# Kenbak-nanoduino.net
KiCad netlist of a schematic drawn in EAGLE
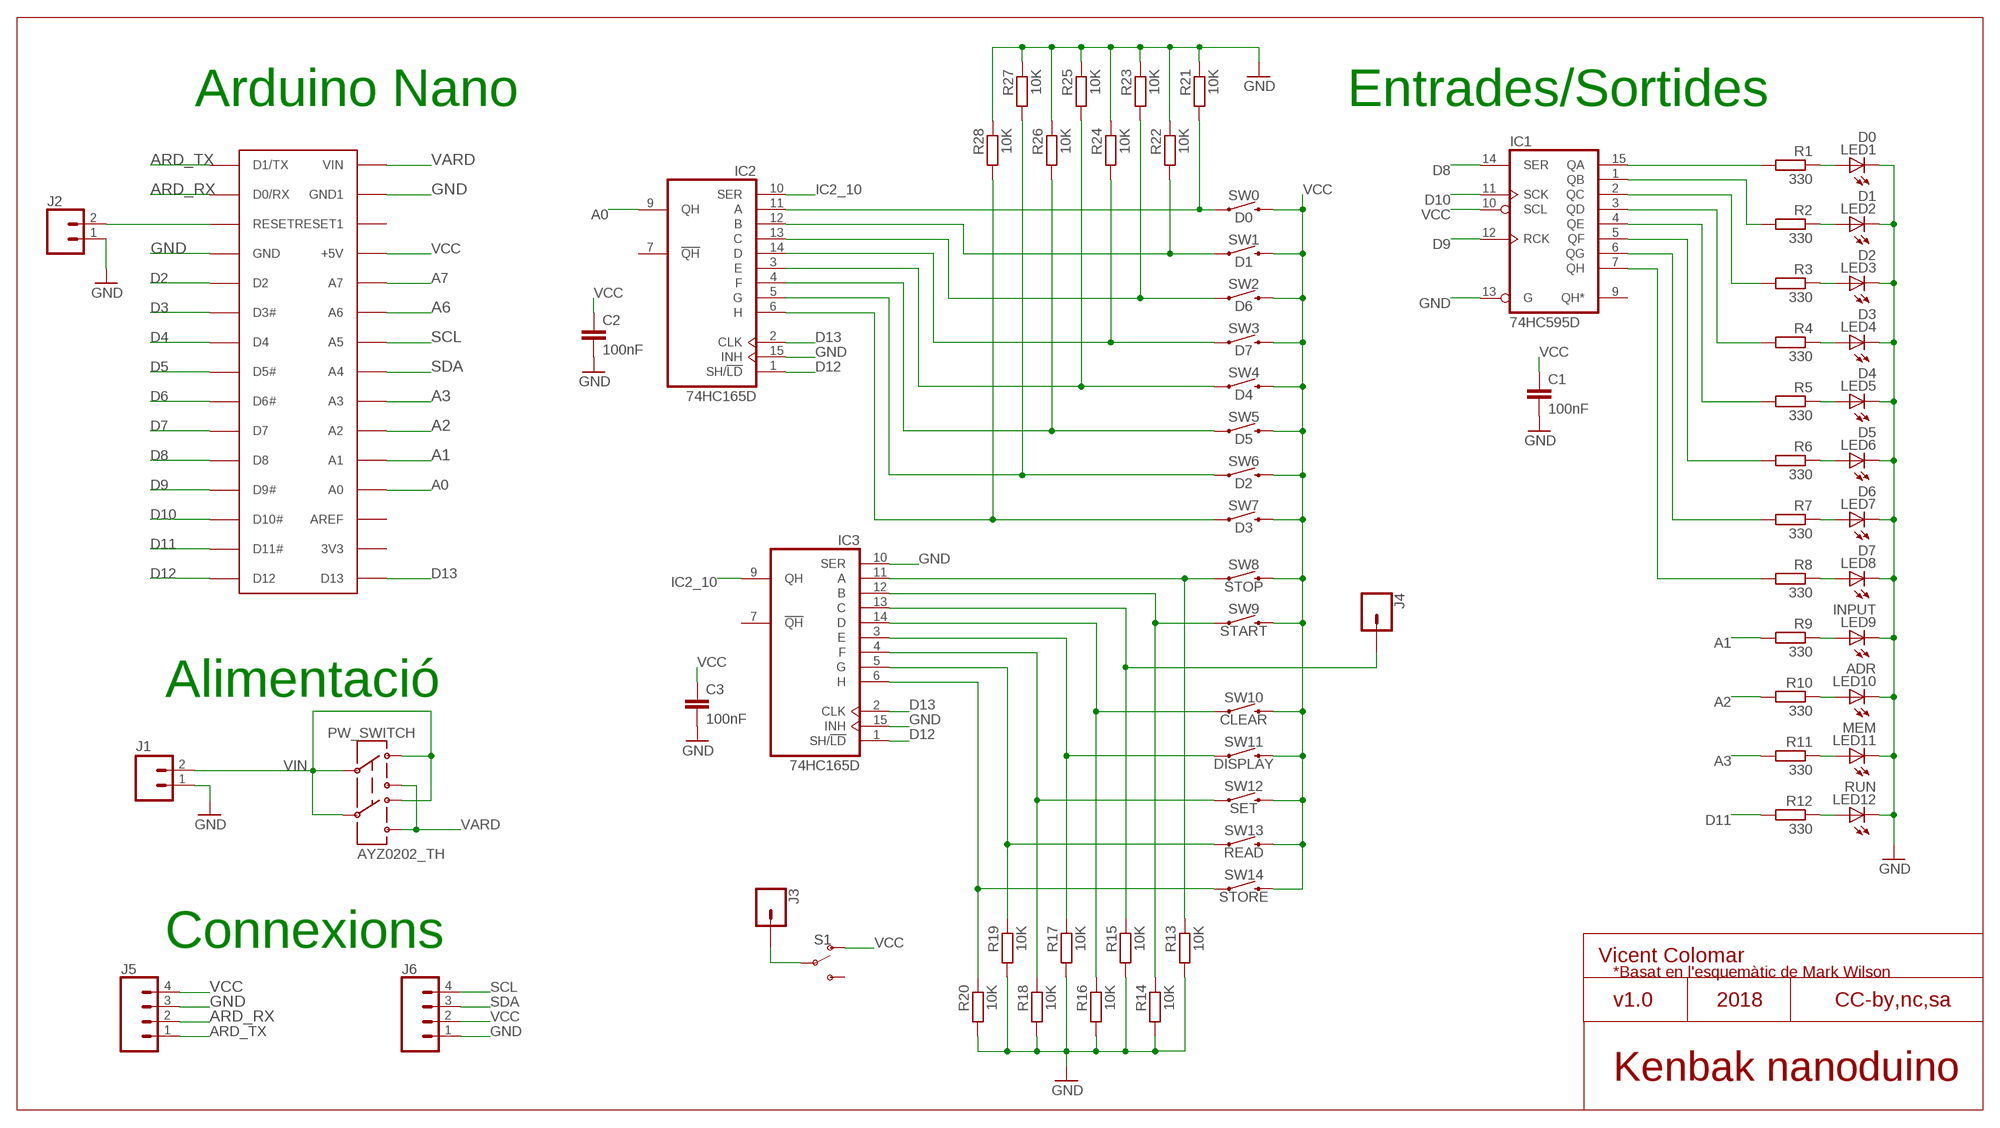
[diagram p0: schematic, sheet 1]

(export (version "E")
  (design (tool "Eeschema 10.0.6"))
  (components
    (comp (ref "ARDUINO")
      (value "NANO")
      (footprint "eagle-import:PDIP-32NOHOLES")
      (libsource (lib "eagle-import") (part "ARDUINONANONOHOLES"))
    )
    (comp (ref "C1")
      (value "100nF")
      (footprint "eagle-import:C1206")
      (libsource (lib "eagle-import") (part "C-EUC1206"))
    )
    (comp (ref "C2")
      (value "100nF")
      (footprint "eagle-import:C1206")
      (libsource (lib "eagle-import") (part "C-EUC1206"))
    )
    (comp (ref "C3")
      (value "100nF")
      (footprint "eagle-import:C1206")
      (libsource (lib "eagle-import") (part "C-EUC1206"))
    )
    (comp (ref "IC1")
      (value "74HC595D")
      (footprint "eagle-import:SO16")
      (libsource (lib "eagle-import") (part "74595DHC"))
    )
    (comp (ref "IC2")
      (value "74HC165D")
      (footprint "eagle-import:SO16")
      (libsource (lib "eagle-import") (part "74165DHC"))
    )
    (comp (ref "IC3")
      (value "74HC165D")
      (footprint "eagle-import:SO16")
      (libsource (lib "eagle-import") (part "74165DHC"))
    )
    (comp (ref "J1")
      (value "M02LOCK_LONGPADS")
      (footprint "eagle-import:1X02_LOCK_LONGPADS")
      (libsource (lib "eagle-import") (part "M02LOCK_LONGPADS"))
    )
    (comp (ref "J2")
      (value "CONN_02")
      (footprint "eagle-import:1X02")
      (libsource (lib "eagle-import") (part "CONN_02"))
    )
    (comp (ref "J3")
      (value "CONN_01")
      (footprint "eagle-import:1X01")
      (libsource (lib "eagle-import") (part "CONN_01"))
    )
    (comp (ref "J4")
      (value "CONN_01")
      (footprint "eagle-import:1X01")
      (libsource (lib "eagle-import") (part "CONN_01"))
    )
    (comp (ref "J5")
      (value "CONN_04")
      (footprint "eagle-import:1X04")
      (libsource (lib "eagle-import") (part "CONN_04"))
    )
    (comp (ref "J6")
      (value "CONN_04")
      (footprint "eagle-import:1X04")
      (libsource (lib "eagle-import") (part "CONN_04"))
    )
    (comp (ref "LED1")
      (value "D0")
      (footprint "eagle-import:LED3MM")
      (libsource (lib "eagle-import") (part "LED3MM"))
    )
    (comp (ref "LED2")
      (value "D1")
      (footprint "eagle-import:LED3MM")
      (libsource (lib "eagle-import") (part "LED3MM"))
    )
    (comp (ref "LED3")
      (value "D2")
      (footprint "eagle-import:LED3MM")
      (libsource (lib "eagle-import") (part "LED3MM"))
    )
    (comp (ref "LED4")
      (value "D3")
      (footprint "eagle-import:LED3MM")
      (libsource (lib "eagle-import") (part "LED3MM"))
    )
    (comp (ref "LED5")
      (value "D4")
      (footprint "eagle-import:LED3MM")
      (libsource (lib "eagle-import") (part "LED3MM"))
    )
    (comp (ref "LED6")
      (value "D5")
      (footprint "eagle-import:LED3MM")
      (libsource (lib "eagle-import") (part "LED3MM"))
    )
    (comp (ref "LED7")
      (value "D6")
      (footprint "eagle-import:LED3MM")
      (libsource (lib "eagle-import") (part "LED3MM"))
    )
    (comp (ref "LED8")
      (value "D7")
      (footprint "eagle-import:LED3MM")
      (libsource (lib "eagle-import") (part "LED3MM"))
    )
    (comp (ref "LED9")
      (value "INPUT")
      (footprint "eagle-import:LED3MM")
      (libsource (lib "eagle-import") (part "LED3MM"))
    )
    (comp (ref "LED10")
      (value "ADR")
      (footprint "eagle-import:LED3MM")
      (libsource (lib "eagle-import") (part "LED3MM"))
    )
    (comp (ref "LED11")
      (value "MEM")
      (footprint "eagle-import:LED3MM")
      (libsource (lib "eagle-import") (part "LED3MM"))
    )
    (comp (ref "LED12")
      (value "RUN")
      (footprint "eagle-import:LED3MM")
      (libsource (lib "eagle-import") (part "LED3MM"))
    )
    (comp (ref "PW_SWITCH")
      (value "AYZ0202_TH")
      (footprint "eagle-import:AYZ0202_TH")
      (libsource (lib "eagle-import") (part "AYZ0202_TH"))
    )
    (comp (ref "R1")
      (value "330")
      (footprint "eagle-import:R1206")
      (libsource (lib "eagle-import") (part "R-EU_R1206"))
    )
    (comp (ref "R2")
      (value "330")
      (footprint "eagle-import:R1206")
      (libsource (lib "eagle-import") (part "R-EU_R1206"))
    )
    (comp (ref "R3")
      (value "330")
      (footprint "eagle-import:R1206")
      (libsource (lib "eagle-import") (part "R-EU_R1206"))
    )
    (comp (ref "R4")
      (value "330")
      (footprint "eagle-import:R1206")
      (libsource (lib "eagle-import") (part "R-EU_R1206"))
    )
    (comp (ref "R5")
      (value "330")
      (footprint "eagle-import:R1206")
      (libsource (lib "eagle-import") (part "R-EU_R1206"))
    )
    (comp (ref "R6")
      (value "330")
      (footprint "eagle-import:R1206")
      (libsource (lib "eagle-import") (part "R-EU_R1206"))
    )
    (comp (ref "R7")
      (value "330")
      (footprint "eagle-import:R1206")
      (libsource (lib "eagle-import") (part "R-EU_R1206"))
    )
    (comp (ref "R8")
      (value "330")
      (footprint "eagle-import:R1206")
      (libsource (lib "eagle-import") (part "R-EU_R1206"))
    )
    (comp (ref "R9")
      (value "330")
      (footprint "eagle-import:R1206")
      (libsource (lib "eagle-import") (part "R-EU_R1206"))
    )
    (comp (ref "R10")
      (value "330")
      (footprint "eagle-import:R1206")
      (libsource (lib "eagle-import") (part "R-EU_R1206"))
    )
    (comp (ref "R11")
      (value "330")
      (footprint "eagle-import:R1206")
      (libsource (lib "eagle-import") (part "R-EU_R1206"))
    )
    (comp (ref "R12")
      (value "330")
      (footprint "eagle-import:R1206")
      (libsource (lib "eagle-import") (part "R-EU_R1206"))
    )
    (comp (ref "R13")
      (value "10K")
      (footprint "eagle-import:R1206")
      (libsource (lib "eagle-import") (part "R-EU_R1206"))
    )
    (comp (ref "R14")
      (value "10K")
      (footprint "eagle-import:R1206")
      (libsource (lib "eagle-import") (part "R-EU_R1206"))
    )
    (comp (ref "R15")
      (value "10K")
      (footprint "eagle-import:R1206")
      (libsource (lib "eagle-import") (part "R-EU_R1206"))
    )
    (comp (ref "R16")
      (value "10K")
      (footprint "eagle-import:R1206")
      (libsource (lib "eagle-import") (part "R-EU_R1206"))
    )
    (comp (ref "R17")
      (value "10K")
      (footprint "eagle-import:R1206")
      (libsource (lib "eagle-import") (part "R-EU_R1206"))
    )
    (comp (ref "R18")
      (value "10K")
      (footprint "eagle-import:R1206")
      (libsource (lib "eagle-import") (part "R-EU_R1206"))
    )
    (comp (ref "R19")
      (value "10K")
      (footprint "eagle-import:R1206")
      (libsource (lib "eagle-import") (part "R-EU_R1206"))
    )
    (comp (ref "R20")
      (value "10K")
      (footprint "eagle-import:R1206")
      (libsource (lib "eagle-import") (part "R-EU_R1206"))
    )
    (comp (ref "R21")
      (value "10K")
      (footprint "eagle-import:R1206")
      (libsource (lib "eagle-import") (part "R-EU_R1206"))
    )
    (comp (ref "R22")
      (value "10K")
      (footprint "eagle-import:R1206")
      (libsource (lib "eagle-import") (part "R-EU_R1206"))
    )
    (comp (ref "R23")
      (value "10K")
      (footprint "eagle-import:R1206")
      (libsource (lib "eagle-import") (part "R-EU_R1206"))
    )
    (comp (ref "R24")
      (value "10K")
      (footprint "eagle-import:R1206")
      (libsource (lib "eagle-import") (part "R-EU_R1206"))
    )
    (comp (ref "R25")
      (value "10K")
      (footprint "eagle-import:R1206")
      (libsource (lib "eagle-import") (part "R-EU_R1206"))
    )
    (comp (ref "R26")
      (value "10K")
      (footprint "eagle-import:R1206")
      (libsource (lib "eagle-import") (part "R-EU_R1206"))
    )
    (comp (ref "R27")
      (value "10K")
      (footprint "eagle-import:R1206")
      (libsource (lib "eagle-import") (part "R-EU_R1206"))
    )
    (comp (ref "R28")
      (value "10K")
      (footprint "eagle-import:R1206")
      (libsource (lib "eagle-import") (part "R-EU_R1206"))
    )
    (comp (ref "S1")
      (value "SWITCH-SPDT-PTH-11.6X4.0MM")
      (footprint "eagle-import:SWITCH_SPDT_PTH_11.6X4.0MM")
      (libsource (lib "eagle-import") (part "SWITCH-SPDT-PTH-11.6X4.0MM"))
    )
    (comp (ref "SW0")
      (value "D0")
      (footprint "eagle-import:TACTILE_SWITCH_PTH_6.0X3.5MM")
      (libsource (lib "eagle-import") (part "BOTOPTH"))
    )
    (comp (ref "SW1")
      (value "D1")
      (footprint "eagle-import:TACTILE_SWITCH_PTH_6.0X3.5MM")
      (libsource (lib "eagle-import") (part "BOTOPTH"))
    )
    (comp (ref "SW2")
      (value "D6")
      (footprint "eagle-import:TACTILE_SWITCH_PTH_6.0X3.5MM")
      (libsource (lib "eagle-import") (part "BOTOPTH"))
    )
    (comp (ref "SW3")
      (value "D7")
      (footprint "eagle-import:TACTILE_SWITCH_PTH_6.0X3.5MM")
      (libsource (lib "eagle-import") (part "BOTOPTH"))
    )
    (comp (ref "SW4")
      (value "D4")
      (footprint "eagle-import:TACTILE_SWITCH_PTH_6.0X3.5MM")
      (libsource (lib "eagle-import") (part "BOTOPTH"))
    )
    (comp (ref "SW5")
      (value "D5")
      (footprint "eagle-import:TACTILE_SWITCH_PTH_6.0X3.5MM")
      (libsource (lib "eagle-import") (part "BOTOPTH"))
    )
    (comp (ref "SW6")
      (value "D2")
      (footprint "eagle-import:TACTILE_SWITCH_PTH_6.0X3.5MM")
      (libsource (lib "eagle-import") (part "BOTOPTH"))
    )
    (comp (ref "SW7")
      (value "D3")
      (footprint "eagle-import:TACTILE_SWITCH_PTH_6.0X3.5MM")
      (libsource (lib "eagle-import") (part "BOTOPTH"))
    )
    (comp (ref "SW8")
      (value "STOP")
      (footprint "eagle-import:TACTILE_SWITCH_PTH_6.0X3.5MM")
      (libsource (lib "eagle-import") (part "BOTOPTH"))
    )
    (comp (ref "SW9")
      (value "START")
      (footprint "eagle-import:TACTILE_SWITCH_PTH_6.0X3.5MM")
      (libsource (lib "eagle-import") (part "BOTOPTH"))
    )
    (comp (ref "SW10")
      (value "CLEAR")
      (footprint "eagle-import:TACTILE_SWITCH_PTH_6.0X3.5MM")
      (libsource (lib "eagle-import") (part "BOTOPTH"))
    )
    (comp (ref "SW11")
      (value "DISPLAY")
      (footprint "eagle-import:TACTILE_SWITCH_PTH_6.0X3.5MM")
      (libsource (lib "eagle-import") (part "BOTOPTH"))
    )
    (comp (ref "SW12")
      (value "SET")
      (footprint "eagle-import:TACTILE_SWITCH_PTH_6.0X3.5MM")
      (libsource (lib "eagle-import") (part "BOTOPTH"))
    )
    (comp (ref "SW13")
      (value "READ")
      (footprint "eagle-import:TACTILE_SWITCH_PTH_6.0X3.5MM")
      (libsource (lib "eagle-import") (part "BOTOPTH"))
    )
    (comp (ref "SW14")
      (value "STORE")
      (footprint "eagle-import:TACTILE_SWITCH_PTH_6.0X3.5MM")
      (libsource (lib "eagle-import") (part "BOTOPTH"))
    )
  )
  (nets
    (net (code "1") (name "/A0") (class "Default")
      (node (ref "ARDUINO") (pin "A0") (pinfunction "A0_A0") (pintype "bidirectional"))
      (node (ref "IC2") (pin "9") (pinfunction "QH_9") (pintype "output"))
    )
    (net (code "2") (name "/A1") (class "Default")
      (node (ref "ARDUINO") (pin "A1") (pinfunction "A1_A1") (pintype "bidirectional"))
      (node (ref "R9") (pin "2") (pinfunction "2_2") (pintype "passive"))
    )
    (net (code "3") (name "/A2") (class "Default")
      (node (ref "ARDUINO") (pin "A2") (pinfunction "A2_A2") (pintype "bidirectional"))
      (node (ref "R10") (pin "2") (pinfunction "2_2") (pintype "passive"))
    )
    (net (code "4") (name "/A3") (class "Default")
      (node (ref "ARDUINO") (pin "A3") (pinfunction "A3_A3") (pintype "bidirectional"))
      (node (ref "R11") (pin "2") (pinfunction "2_2") (pintype "passive"))
    )
    (net (code "5") (name "/A6") (class "Default")
      (node (ref "ARDUINO") (pin "A6") (pinfunction "A6_A6") (pintype "bidirectional"))
    )
    (net (code "6") (name "/A7") (class "Default")
      (node (ref "ARDUINO") (pin "A7") (pinfunction "A7_A7") (pintype "bidirectional"))
    )
    (net (code "7") (name "/ARD_RX") (class "Default")
      (node (ref "ARDUINO") (pin "D0/RX") (pinfunction "D0/RX_D0/RX") (pintype "bidirectional"))
      (node (ref "J5") (pin "2") (pinfunction "2_2") (pintype "passive"))
    )
    (net (code "8") (name "/ARD_TX") (class "Default")
      (node (ref "ARDUINO") (pin "D1/TX") (pinfunction "D1/TX_D1/TX") (pintype "bidirectional"))
      (node (ref "J5") (pin "1") (pinfunction "1_1") (pintype "passive"))
    )
    (net (code "9") (name "/D2") (class "Default")
      (node (ref "ARDUINO") (pin "D2") (pinfunction "D2_D2") (pintype "bidirectional"))
    )
    (net (code "10") (name "/D3") (class "Default")
      (node (ref "ARDUINO") (pin "D3") (pinfunction "D3#_D3") (pintype "bidirectional"))
    )
    (net (code "11") (name "/D4") (class "Default")
      (node (ref "ARDUINO") (pin "D4") (pinfunction "D4_D4") (pintype "bidirectional"))
    )
    (net (code "12") (name "/D5") (class "Default")
      (node (ref "ARDUINO") (pin "D5") (pinfunction "D5#_D5") (pintype "bidirectional"))
    )
    (net (code "13") (name "/D6") (class "Default")
      (node (ref "ARDUINO") (pin "D6") (pinfunction "D6#_D6") (pintype "bidirectional"))
    )
    (net (code "14") (name "/D7") (class "Default")
      (node (ref "ARDUINO") (pin "D7") (pinfunction "D7_D7") (pintype "bidirectional"))
    )
    (net (code "15") (name "/D8") (class "Default")
      (node (ref "ARDUINO") (pin "D8") (pinfunction "D8_D8") (pintype "bidirectional"))
      (node (ref "IC1") (pin "14") (pinfunction "SER_14") (pintype "input"))
    )
    (net (code "16") (name "/D9") (class "Default")
      (node (ref "ARDUINO") (pin "D9") (pinfunction "D9#_D9") (pintype "bidirectional"))
      (node (ref "IC1") (pin "12") (pinfunction "RCK_12") (pintype "input"))
    )
    (net (code "17") (name "/D10") (class "Default")
      (node (ref "ARDUINO") (pin "D10") (pinfunction "D10#_D10") (pintype "bidirectional"))
      (node (ref "IC1") (pin "11") (pinfunction "SCK_11") (pintype "input"))
    )
    (net (code "18") (name "/D11") (class "Default")
      (node (ref "ARDUINO") (pin "D11") (pinfunction "D11#_D11") (pintype "bidirectional"))
      (node (ref "R12") (pin "2") (pinfunction "2_2") (pintype "passive"))
    )
    (net (code "19") (name "/D12") (class "Default")
      (node (ref "ARDUINO") (pin "D12") (pinfunction "D12_D12") (pintype "bidirectional"))
      (node (ref "IC2") (pin "1") (pinfunction "SH/~{LD}_1") (pintype "input"))
      (node (ref "IC3") (pin "1") (pinfunction "SH/~{LD}_1") (pintype "input"))
    )
    (net (code "20") (name "/D13") (class "Default")
      (node (ref "ARDUINO") (pin "D13") (pinfunction "D13_D13") (pintype "bidirectional"))
      (node (ref "IC2") (pin "2") (pinfunction "CLK_2") (pintype "input"))
      (node (ref "IC3") (pin "2") (pinfunction "CLK_2") (pintype "input"))
    )
    (net (code "21") (name "/IC2_10") (class "Default")
      (node (ref "IC2") (pin "10") (pinfunction "SER_10") (pintype "input"))
      (node (ref "IC3") (pin "9") (pinfunction "QH_9") (pintype "output"))
    )
    (net (code "22") (name "/SCL") (class "Default")
      (node (ref "ARDUINO") (pin "A5") (pinfunction "A5_A5") (pintype "bidirectional"))
      (node (ref "J6") (pin "4") (pinfunction "4_4") (pintype "passive"))
    )
    (net (code "23") (name "/SDA") (class "Default")
      (node (ref "ARDUINO") (pin "A4") (pinfunction "A4_A4") (pintype "bidirectional"))
      (node (ref "J6") (pin "3") (pinfunction "3_3") (pintype "passive"))
    )
    (net (code "24") (name "/VARD") (class "Default")
      (node (ref "ARDUINO") (pin "VIN") (pinfunction "VIN_VIN") (pintype "bidirectional"))
      (node (ref "PW_SWITCH") (pin "B1") (pinfunction "B1_B1") (pintype "bidirectional"))
      (node (ref "PW_SWITCH") (pin "B2") (pinfunction "B2_B2") (pintype "bidirectional"))
    )
    (net (code "25") (name "/VCC") (class "Default")
      (node (ref "ARDUINO") (pin "+5V") (pinfunction "+5V_+5V") (pintype "bidirectional"))
      (node (ref "C1") (pin "1") (pinfunction "1_1") (pintype "passive"))
      (node (ref "C2") (pin "1") (pinfunction "1_1") (pintype "passive"))
      (node (ref "C3") (pin "1") (pinfunction "1_1") (pintype "passive"))
      (node (ref "IC1") (pin "10") (pinfunction "SCL_10") (pintype "input"))
      (node (ref "J5") (pin "4") (pinfunction "4_4") (pintype "passive"))
      (node (ref "J6") (pin "2") (pinfunction "2_2") (pintype "passive"))
      (node (ref "S1") (pin "1") (pinfunction "O_1") (pintype "passive"))
      (node (ref "SW0") (pin "P$2") (pinfunction "2_P$2") (pintype "passive"))
      (node (ref "SW1") (pin "P$2") (pinfunction "2_P$2") (pintype "passive"))
      (node (ref "SW10") (pin "P$2") (pinfunction "2_P$2") (pintype "passive"))
      (node (ref "SW11") (pin "P$2") (pinfunction "2_P$2") (pintype "passive"))
      (node (ref "SW12") (pin "P$2") (pinfunction "2_P$2") (pintype "passive"))
      (node (ref "SW13") (pin "P$2") (pinfunction "2_P$2") (pintype "passive"))
      (node (ref "SW14") (pin "P$2") (pinfunction "2_P$2") (pintype "passive"))
      (node (ref "SW2") (pin "P$2") (pinfunction "2_P$2") (pintype "passive"))
      (node (ref "SW3") (pin "P$2") (pinfunction "2_P$2") (pintype "passive"))
      (node (ref "SW4") (pin "P$2") (pinfunction "2_P$2") (pintype "passive"))
      (node (ref "SW5") (pin "P$2") (pinfunction "2_P$2") (pintype "passive"))
      (node (ref "SW6") (pin "P$2") (pinfunction "2_P$2") (pintype "passive"))
      (node (ref "SW7") (pin "P$2") (pinfunction "2_P$2") (pintype "passive"))
      (node (ref "SW8") (pin "P$2") (pinfunction "2_P$2") (pintype "passive"))
      (node (ref "SW9") (pin "P$2") (pinfunction "2_P$2") (pintype "passive"))
    )
    (net (code "26") (name "/VIN") (class "Default")
      (node (ref "J1") (pin "2") (pinfunction "2_2") (pintype "passive"))
      (node (ref "PW_SWITCH") (pin "C1") (pinfunction "C1_C1") (pintype "bidirectional"))
      (node (ref "PW_SWITCH") (pin "C2") (pinfunction "C2_C2") (pintype "bidirectional"))
      (node (ref "PW_SWITCH") (pin "D1") (pinfunction "D1_D1") (pintype "bidirectional"))
      (node (ref "PW_SWITCH") (pin "D2") (pinfunction "D2_D2") (pintype "bidirectional"))
    )
    (net (code "27") (name "GND") (class "Default")
      (node (ref "ARDUINO") (pin "GND") (pinfunction "GND_GND") (pintype "bidirectional"))
      (node (ref "ARDUINO") (pin "GND1") (pinfunction "GND1_GND1") (pintype "bidirectional"))
      (node (ref "C1") (pin "2") (pinfunction "2_2") (pintype "passive"))
      (node (ref "C2") (pin "2") (pinfunction "2_2") (pintype "passive"))
      (node (ref "C3") (pin "2") (pinfunction "2_2") (pintype "passive"))
      (node (ref "IC1") (pin "13") (pinfunction "G_13") (pintype "input"))
      (node (ref "IC2") (pin "15") (pinfunction "INH_15") (pintype "input"))
      (node (ref "IC3") (pin "10") (pinfunction "SER_10") (pintype "input"))
      (node (ref "IC3") (pin "15") (pinfunction "INH_15") (pintype "input"))
      (node (ref "J1") (pin "1") (pinfunction "1_1") (pintype "passive"))
      (node (ref "J2") (pin "1") (pinfunction "1_1") (pintype "passive"))
      (node (ref "J5") (pin "3") (pinfunction "3_3") (pintype "passive"))
      (node (ref "J6") (pin "1") (pinfunction "1_1") (pintype "passive"))
      (node (ref "LED1") (pin "K") (pinfunction "C_K") (pintype "passive"))
      (node (ref "LED10") (pin "K") (pinfunction "C_K") (pintype "passive"))
      (node (ref "LED11") (pin "K") (pinfunction "C_K") (pintype "passive"))
      (node (ref "LED12") (pin "K") (pinfunction "C_K") (pintype "passive"))
      (node (ref "LED2") (pin "K") (pinfunction "C_K") (pintype "passive"))
      (node (ref "LED3") (pin "K") (pinfunction "C_K") (pintype "passive"))
      (node (ref "LED4") (pin "K") (pinfunction "C_K") (pintype "passive"))
      (node (ref "LED5") (pin "K") (pinfunction "C_K") (pintype "passive"))
      (node (ref "LED6") (pin "K") (pinfunction "C_K") (pintype "passive"))
      (node (ref "LED7") (pin "K") (pinfunction "C_K") (pintype "passive"))
      (node (ref "LED8") (pin "K") (pinfunction "C_K") (pintype "passive"))
      (node (ref "LED9") (pin "K") (pinfunction "C_K") (pintype "passive"))
      (node (ref "R13") (pin "2") (pinfunction "2_2") (pintype "passive"))
      (node (ref "R14") (pin "2") (pinfunction "2_2") (pintype "passive"))
      (node (ref "R15") (pin "2") (pinfunction "2_2") (pintype "passive"))
      (node (ref "R16") (pin "2") (pinfunction "2_2") (pintype "passive"))
      (node (ref "R17") (pin "2") (pinfunction "2_2") (pintype "passive"))
      (node (ref "R18") (pin "2") (pinfunction "2_2") (pintype "passive"))
      (node (ref "R19") (pin "2") (pinfunction "2_2") (pintype "passive"))
      (node (ref "R20") (pin "2") (pinfunction "2_2") (pintype "passive"))
      (node (ref "R21") (pin "1") (pinfunction "1_1") (pintype "passive"))
      (node (ref "R22") (pin "1") (pinfunction "1_1") (pintype "passive"))
      (node (ref "R23") (pin "1") (pinfunction "1_1") (pintype "passive"))
      (node (ref "R24") (pin "1") (pinfunction "1_1") (pintype "passive"))
      (node (ref "R25") (pin "1") (pinfunction "1_1") (pintype "passive"))
      (node (ref "R26") (pin "1") (pinfunction "1_1") (pintype "passive"))
      (node (ref "R27") (pin "1") (pinfunction "1_1") (pintype "passive"))
      (node (ref "R28") (pin "1") (pinfunction "1_1") (pintype "passive"))
    )
    (net (code "28") (name "Net-(ARDUINO-PadRESET)") (class "Default")
      (node (ref "ARDUINO") (pin "RESET") (pinfunction "RESET_RESET") (pintype "bidirectional"))
      (node (ref "J2") (pin "2") (pinfunction "2_2") (pintype "passive"))
    )
    (net (code "29") (name "Net-(IC1A-QA)") (class "Default")
      (node (ref "IC1") (pin "15") (pinfunction "QA_15") (pintype "tri_state"))
      (node (ref "R1") (pin "2") (pinfunction "2_2") (pintype "passive"))
    )
    (net (code "30") (name "Net-(IC1A-QB)") (class "Default")
      (node (ref "IC1") (pin "1") (pinfunction "QB_1") (pintype "tri_state"))
      (node (ref "R2") (pin "2") (pinfunction "2_2") (pintype "passive"))
    )
    (net (code "31") (name "Net-(IC1A-QC)") (class "Default")
      (node (ref "IC1") (pin "2") (pinfunction "QC_2") (pintype "tri_state"))
      (node (ref "R3") (pin "2") (pinfunction "2_2") (pintype "passive"))
    )
    (net (code "32") (name "Net-(IC1A-QD)") (class "Default")
      (node (ref "IC1") (pin "3") (pinfunction "QD_3") (pintype "tri_state"))
      (node (ref "R4") (pin "2") (pinfunction "2_2") (pintype "passive"))
    )
    (net (code "33") (name "Net-(IC1A-QE)") (class "Default")
      (node (ref "IC1") (pin "4") (pinfunction "QE_4") (pintype "tri_state"))
      (node (ref "R5") (pin "2") (pinfunction "2_2") (pintype "passive"))
    )
    (net (code "34") (name "Net-(IC1A-QF)") (class "Default")
      (node (ref "IC1") (pin "5") (pinfunction "QF_5") (pintype "tri_state"))
      (node (ref "R6") (pin "2") (pinfunction "2_2") (pintype "passive"))
    )
    (net (code "35") (name "Net-(IC1A-QG)") (class "Default")
      (node (ref "IC1") (pin "6") (pinfunction "QG_6") (pintype "tri_state"))
      (node (ref "R7") (pin "2") (pinfunction "2_2") (pintype "passive"))
    )
    (net (code "36") (name "Net-(IC1A-QH)") (class "Default")
      (node (ref "IC1") (pin "7") (pinfunction "QH_7") (pintype "tri_state"))
      (node (ref "R8") (pin "2") (pinfunction "2_2") (pintype "passive"))
    )
    (net (code "37") (name "Net-(IC2A-A)") (class "Default")
      (node (ref "IC2") (pin "11") (pinfunction "A_11") (pintype "input"))
      (node (ref "R21") (pin "2") (pinfunction "2_2") (pintype "passive"))
      (node (ref "SW0") (pin "P$1") (pinfunction "1_P$1") (pintype "passive"))
    )
    (net (code "38") (name "Net-(IC2A-B)") (class "Default")
      (node (ref "IC2") (pin "12") (pinfunction "B_12") (pintype "input"))
      (node (ref "R22") (pin "2") (pinfunction "2_2") (pintype "passive"))
      (node (ref "SW1") (pin "P$1") (pinfunction "1_P$1") (pintype "passive"))
    )
    (net (code "39") (name "Net-(IC2A-C)") (class "Default")
      (node (ref "IC2") (pin "13") (pinfunction "C_13") (pintype "input"))
      (node (ref "R23") (pin "2") (pinfunction "2_2") (pintype "passive"))
      (node (ref "SW2") (pin "P$1") (pinfunction "1_P$1") (pintype "passive"))
    )
    (net (code "40") (name "Net-(IC2A-D)") (class "Default")
      (node (ref "IC2") (pin "14") (pinfunction "D_14") (pintype "input"))
      (node (ref "R24") (pin "2") (pinfunction "2_2") (pintype "passive"))
      (node (ref "SW3") (pin "P$1") (pinfunction "1_P$1") (pintype "passive"))
    )
    (net (code "41") (name "Net-(IC2A-E)") (class "Default")
      (node (ref "IC2") (pin "3") (pinfunction "E_3") (pintype "input"))
      (node (ref "R25") (pin "2") (pinfunction "2_2") (pintype "passive"))
      (node (ref "SW4") (pin "P$1") (pinfunction "1_P$1") (pintype "passive"))
    )
    (net (code "42") (name "Net-(IC2A-F)") (class "Default")
      (node (ref "IC2") (pin "4") (pinfunction "F_4") (pintype "input"))
      (node (ref "R26") (pin "2") (pinfunction "2_2") (pintype "passive"))
      (node (ref "SW5") (pin "P$1") (pinfunction "1_P$1") (pintype "passive"))
    )
    (net (code "43") (name "Net-(IC2A-G)") (class "Default")
      (node (ref "IC2") (pin "5") (pinfunction "G_5") (pintype "input"))
      (node (ref "R27") (pin "2") (pinfunction "2_2") (pintype "passive"))
      (node (ref "SW6") (pin "P$1") (pinfunction "1_P$1") (pintype "passive"))
    )
    (net (code "44") (name "Net-(IC2A-H)") (class "Default")
      (node (ref "IC2") (pin "6") (pinfunction "H_6") (pintype "input"))
      (node (ref "R28") (pin "2") (pinfunction "2_2") (pintype "passive"))
      (node (ref "SW7") (pin "P$1") (pinfunction "1_P$1") (pintype "passive"))
    )
    (net (code "45") (name "Net-(IC3A-A)") (class "Default")
      (node (ref "IC3") (pin "11") (pinfunction "A_11") (pintype "input"))
      (node (ref "R13") (pin "1") (pinfunction "1_1") (pintype "passive"))
      (node (ref "SW8") (pin "P$1") (pinfunction "1_P$1") (pintype "passive"))
    )
    (net (code "46") (name "Net-(IC3A-B)") (class "Default")
      (node (ref "IC3") (pin "12") (pinfunction "B_12") (pintype "input"))
      (node (ref "R14") (pin "1") (pinfunction "1_1") (pintype "passive"))
      (node (ref "SW9") (pin "P$1") (pinfunction "1_P$1") (pintype "passive"))
    )
    (net (code "47") (name "Net-(IC3A-C)") (class "Default")
      (node (ref "IC3") (pin "13") (pinfunction "C_13") (pintype "input"))
      (node (ref "J4") (pin "1") (pinfunction "1_1") (pintype "passive"))
      (node (ref "R15") (pin "1") (pinfunction "1_1") (pintype "passive"))
    )
    (net (code "48") (name "Net-(IC3A-D)") (class "Default")
      (node (ref "IC3") (pin "14") (pinfunction "D_14") (pintype "input"))
      (node (ref "R16") (pin "1") (pinfunction "1_1") (pintype "passive"))
      (node (ref "SW10") (pin "P$1") (pinfunction "1_P$1") (pintype "passive"))
    )
    (net (code "49") (name "Net-(IC3A-E)") (class "Default")
      (node (ref "IC3") (pin "3") (pinfunction "E_3") (pintype "input"))
      (node (ref "R17") (pin "1") (pinfunction "1_1") (pintype "passive"))
      (node (ref "SW11") (pin "P$1") (pinfunction "1_P$1") (pintype "passive"))
    )
    (net (code "50") (name "Net-(IC3A-F)") (class "Default")
      (node (ref "IC3") (pin "4") (pinfunction "F_4") (pintype "input"))
      (node (ref "R18") (pin "1") (pinfunction "1_1") (pintype "passive"))
      (node (ref "SW12") (pin "P$1") (pinfunction "1_P$1") (pintype "passive"))
    )
    (net (code "51") (name "Net-(IC3A-G)") (class "Default")
      (node (ref "IC3") (pin "5") (pinfunction "G_5") (pintype "input"))
      (node (ref "R19") (pin "1") (pinfunction "1_1") (pintype "passive"))
      (node (ref "SW13") (pin "P$1") (pinfunction "1_P$1") (pintype "passive"))
    )
    (net (code "52") (name "Net-(IC3A-H)") (class "Default")
      (node (ref "IC3") (pin "6") (pinfunction "H_6") (pintype "input"))
      (node (ref "R20") (pin "1") (pinfunction "1_1") (pintype "passive"))
      (node (ref "SW14") (pin "P$1") (pinfunction "1_P$1") (pintype "passive"))
    )
    (net (code "53") (name "Net-(LED1-PadA)") (class "Default")
      (node (ref "LED1") (pin "A") (pinfunction "A_A") (pintype "passive"))
      (node (ref "R1") (pin "1") (pinfunction "1_1") (pintype "passive"))
    )
    (net (code "54") (name "Net-(LED2-PadA)") (class "Default")
      (node (ref "LED2") (pin "A") (pinfunction "A_A") (pintype "passive"))
      (node (ref "R2") (pin "1") (pinfunction "1_1") (pintype "passive"))
    )
    (net (code "55") (name "Net-(LED3-PadA)") (class "Default")
      (node (ref "LED3") (pin "A") (pinfunction "A_A") (pintype "passive"))
      (node (ref "R3") (pin "1") (pinfunction "1_1") (pintype "passive"))
    )
    (net (code "56") (name "Net-(LED4-PadA)") (class "Default")
      (node (ref "LED4") (pin "A") (pinfunction "A_A") (pintype "passive"))
      (node (ref "R4") (pin "1") (pinfunction "1_1") (pintype "passive"))
    )
    (net (code "57") (name "Net-(LED5-PadA)") (class "Default")
      (node (ref "LED5") (pin "A") (pinfunction "A_A") (pintype "passive"))
      (node (ref "R5") (pin "1") (pinfunction "1_1") (pintype "passive"))
    )
    (net (code "58") (name "Net-(LED6-PadA)") (class "Default")
      (node (ref "LED6") (pin "A") (pinfunction "A_A") (pintype "passive"))
      (node (ref "R6") (pin "1") (pinfunction "1_1") (pintype "passive"))
    )
    (net (code "59") (name "Net-(LED7-PadA)") (class "Default")
      (node (ref "LED7") (pin "A") (pinfunction "A_A") (pintype "passive"))
      (node (ref "R7") (pin "1") (pinfunction "1_1") (pintype "passive"))
    )
    (net (code "60") (name "Net-(LED8-PadA)") (class "Default")
      (node (ref "LED8") (pin "A") (pinfunction "A_A") (pintype "passive"))
      (node (ref "R8") (pin "1") (pinfunction "1_1") (pintype "passive"))
    )
    (net (code "61") (name "Net-(LED9-PadA)") (class "Default")
      (node (ref "LED9") (pin "A") (pinfunction "A_A") (pintype "passive"))
      (node (ref "R9") (pin "1") (pinfunction "1_1") (pintype "passive"))
    )
    (net (code "62") (name "Net-(LED10-PadA)") (class "Default")
      (node (ref "LED10") (pin "A") (pinfunction "A_A") (pintype "passive"))
      (node (ref "R10") (pin "1") (pinfunction "1_1") (pintype "passive"))
    )
    (net (code "63") (name "Net-(LED11-PadA)") (class "Default")
      (node (ref "LED11") (pin "A") (pinfunction "A_A") (pintype "passive"))
      (node (ref "R11") (pin "1") (pinfunction "1_1") (pintype "passive"))
    )
    (net (code "64") (name "Net-(LED12-PadA)") (class "Default")
      (node (ref "LED12") (pin "A") (pinfunction "A_A") (pintype "passive"))
      (node (ref "R12") (pin "1") (pinfunction "1_1") (pintype "passive"))
    )
    (net (code "65") (name "Net-(S1-P)") (class "Default")
      (node (ref "J3") (pin "1") (pinfunction "1_1") (pintype "passive"))
      (node (ref "S1") (pin "2") (pinfunction "P_2") (pintype "passive"))
    )
    (net (code "66") (name "unconnected-(ARDUINO-Pad3V3)") (class "Default")
      (node (ref "ARDUINO") (pin "3V3") (pinfunction "3V3_3V3") (pintype "bidirectional"))
    )
    (net (code "67") (name "unconnected-(ARDUINO-PadAREF)") (class "Default")
      (node (ref "ARDUINO") (pin "AREF") (pinfunction "AREF_AREF") (pintype "bidirectional"))
    )
    (net (code "68") (name "unconnected-(ARDUINO-PadRESET1)") (class "Default")
      (node (ref "ARDUINO") (pin "RESET1") (pinfunction "RESET1_RESET1") (pintype "bidirectional"))
    )
    (net (code "69") (name "unconnected-(IC1A-QH*-Pad9)") (class "Default")
      (node (ref "IC1") (pin "9") (pinfunction "QH*_9") (pintype "tri_state"))
    )
    (net (code "70") (name "unconnected-(IC2A-~{QH}-Pad7)") (class "Default")
      (node (ref "IC2") (pin "7") (pinfunction "~{QH}_7") (pintype "output"))
    )
    (net (code "71") (name "unconnected-(IC3A-~{QH}-Pad7)") (class "Default")
      (node (ref "IC3") (pin "7") (pinfunction "~{QH}_7") (pintype "output"))
    )
    (net (code "72") (name "unconnected-(S1-S-Pad3)") (class "Default")
      (node (ref "S1") (pin "3") (pinfunction "S_3") (pintype "passive"))
    )
  )
)
